# ESP32_LHCbit.net
KiCad netlist of a schematic drawn in Altium Designer
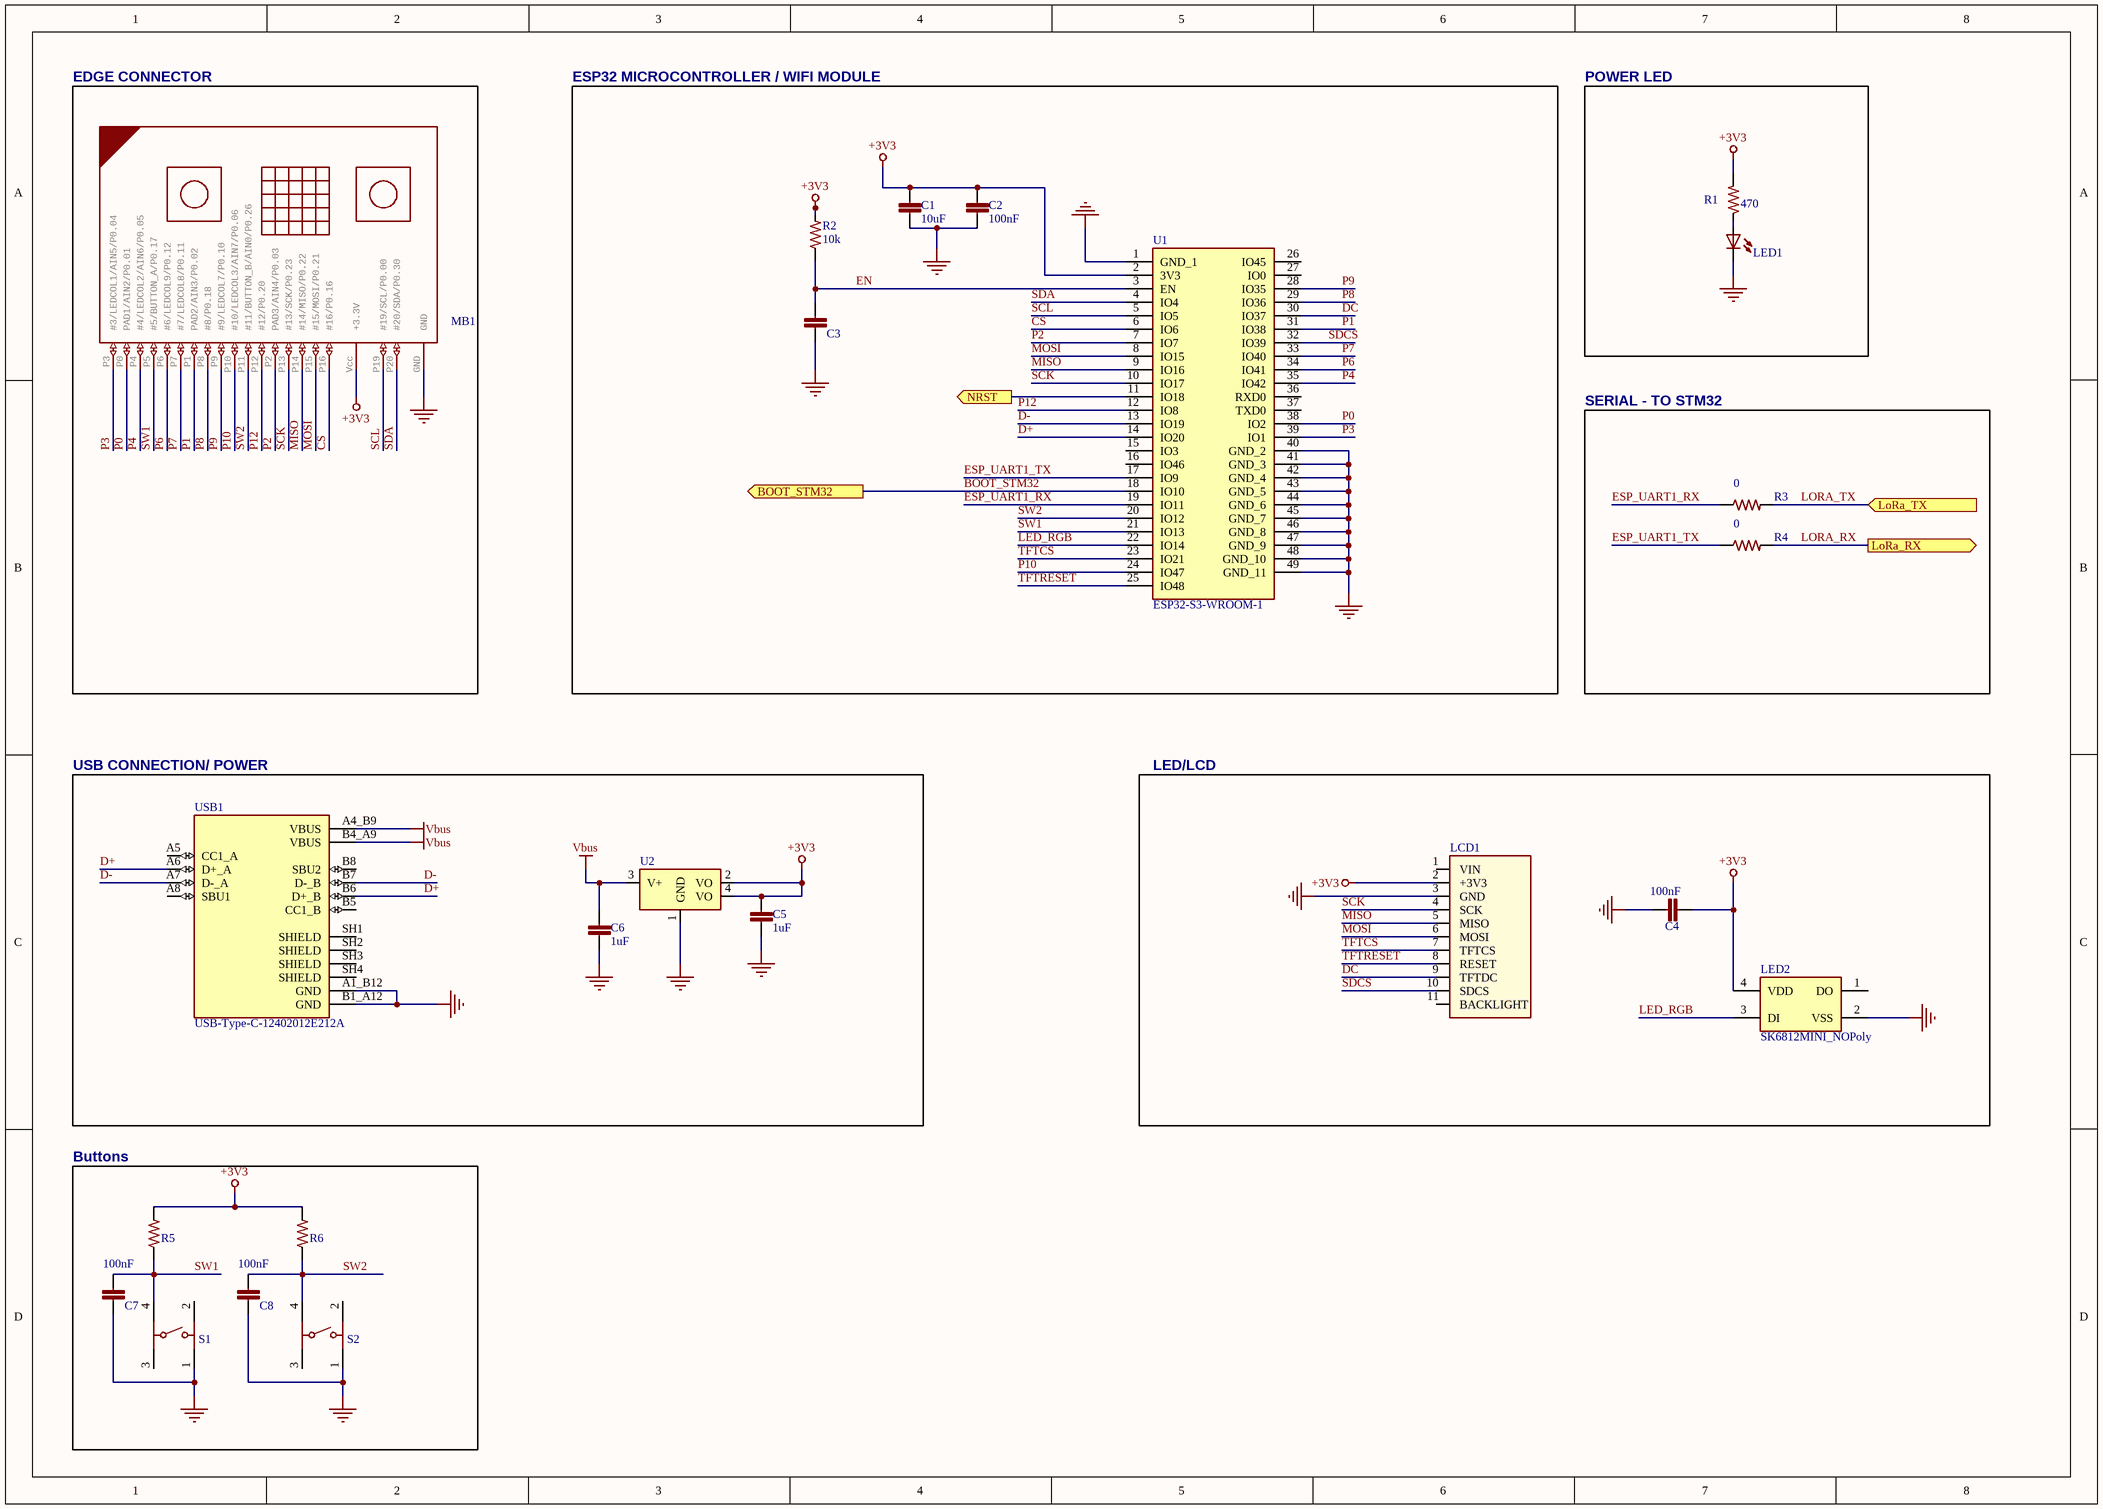
[diagram p0: ESP32_LHCbit.SchDoc]

(export (version "E")
  (design (tool "Eeschema 10.0.6"))
  (components
    (comp (ref "C1")
      (value "10uF")
      (footprint "C0603")
      (fields (field (name "PART NUMBER") "CL10A106KP8NNNC") (field (name "Comment") "C-EUC0603"))
      (libsource (lib "rcl") (part "C-EUC0603"))
    )
    (comp (ref "C2")
      (value "100nF")
      (footprint "C0603")
      (fields (field (name "PART NUMBER") "CC0603KRX7R9BB104") (field (name "Comment") "C-EUC0603"))
      (libsource (lib "rcl") (part "C-EUC0603"))
    )
    (comp (ref "C3")
      (value "C-EUC0402")
      (footprint "C0402")
      (fields (field (name "PART NUMBER") "C0402C104K8"))
      (libsource (lib "rcl") (part "C-EUC0402"))
    )
    (comp (ref "C4")
      (value "100nF")
      (footprint "C0402")
      (fields (field (name "PART NUMBER") "C0402C104K8") (field (name "Comment") "C-EUC0402"))
      (libsource (lib "") (part "C-EUC0402_1"))
    )
    (comp (ref "C5")
      (value "1uF")
      (footprint "C0603")
      (fields (field (name "PART NUMBER") "CL10A105KO8NNNC") (field (name "Comment") "C-EUC0603"))
      (libsource (lib "") (part "C-EUC0603_1"))
    )
    (comp (ref "C6")
      (value "1uF")
      (footprint "C0603")
      (fields (field (name "PART NUMBER") "CL10A105KO8NNNC") (field (name "Comment") "C-EUC0603"))
      (libsource (lib "") (part "C-EUC0603_1"))
    )
    (comp (ref "C7")
      (value "100nF")
      (footprint "C0402")
      (fields (field (name "PART NUMBER") "C0402C104K8") (field (name "Comment") "C-EUC0402"))
      (libsource (lib "rcl") (part "C-EUC0402"))
    )
    (comp (ref "C8")
      (value "100nF")
      (footprint "C0402")
      (fields (field (name "PART NUMBER") "C0402C104K8") (field (name "Comment") "C-EUC0402"))
      (libsource (lib "rcl") (part "C-EUC0402"))
    )
    (comp (ref "LCD1")
      (value "Adafruit 0.96\"  TFT LCD")
      (footprint "ADafruit 0.96 Display")
      (libsource (lib "TE") (part "Adafruit 0.96{dblquote}  TFT LCD"))
    )
    (comp (ref "LED1")
      (value "~")
      (footprint "CHIPLED_0805")
      (fields (field (name "PART NUMBER") "AP2012EC"))
      (libsource (lib "led") (part "LEDCHIPLED_0805"))
    )
    (comp (ref "LED2")
      (value "SK6812MINI_NOPoly")
      (footprint "WS2812BMINI_no_poly")
      (description "SMD RGB (WS2812/SK6812MINI) 3535")
      (fields (field (name "PART NUMBER") "SK6812MINI"))
      (libsource (lib "led") (part "SK6812MINI_NOPoly"))
    )
    (comp (ref "MB1")
      (value "MICRO:BIT_EDGE")
      (footprint "MICROBIT_EDGE")
      (libsource (lib "TE") (part "MICRO{colon}BIT_EDGE"))
    )
    (comp (ref "R1")
      (value "470")
      (footprint "R0603")
      (fields (field (name "PART NUMBER") "RC0603FR-07470RL") (field (name "Comment") "R-US_R0603"))
      (libsource (lib "rcl") (part "R-US_R0603"))
    )
    (comp (ref "R2")
      (value "10k")
      (footprint "R0402")
      (fields (field (name "PART NUMBER") "RC0402FR-0710KL") (field (name "Comment") "R-US_R0402"))
      (libsource (lib "rcl") (part "R-US_R0402"))
    )
    (comp (ref "R3")
      (value "0")
      (footprint "R0402")
      (fields (field (name "PART NUMBER") "PA0402-R-070RL") (field (name "Comment") "R-US_R0402"))
      (libsource (lib "rcl") (part "R-US_R0402"))
    )
    (comp (ref "R4")
      (value "0")
      (footprint "R0402")
      (fields (field (name "PART NUMBER") "PA0402-R-070RL") (field (name "Comment") "R-US_R0402"))
      (libsource (lib "rcl") (part "R-US_R0402"))
    )
    (comp (ref "R5")
      (value "R-US_R0402")
      (footprint "R0402")
      (fields (field (name "PART NUMBER") "RC0402FR-0710KL"))
      (libsource (lib "rcl") (part "R-US_R0402"))
    )
    (comp (ref "R6")
      (value "R-US_R0402")
      (footprint "R0402")
      (fields (field (name "PART NUMBER") "RC0402FR-0710KL"))
      (libsource (lib "rcl") (part "R-US_R0402"))
    )
    (comp (ref "S1")
      (value "DTSM-6")
      (footprint "4301x20438x6_6x6x4.3_DTSM-6")
      (description "WS-TASV 6x6mm Tact Switch, SMD version")
      (libsource (lib "Switches") (part "DTSM-6"))
    )
    (comp (ref "S2")
      (value "DTSM-6")
      (footprint "4301x20438x6_6x6x4.3_DTSM-6")
      (description "WS-TASV 6x6mm Tact Switch, SMD version")
      (libsource (lib "Switches") (part "DTSM-6"))
    )
    (comp (ref "U1")
      (value "ESP32-S3-WROOM-1")
      (footprint "ESP32S3WROOM1N16R2")
      (description "Integrated Circuit")
      (fields (field (name "PART NUMBER") "ESP32-S3-WROOM-1-N16R2"))
      (libsource (lib "TE") (part "ESP32-S3-WROOM-1"))
    )
    (comp (ref "U2")
      (value "NCP1117LP")
      (footprint "SOT223")
      (fields (field (name "PART NUMBER") "TLV1117LV33DCYR"))
      (libsource (lib "TE") (part "NCP1117LP"))
    )
    (comp (ref "USB1")
      (value "USB-Type-C-12402012E212A")
      (footprint "AMPHENOL_12402012E212A")
      (description "USB2.0, Type C")
      (fields (field (name "PART NUMBER") "TYPEC-304-ACP16"))
      (libsource (lib "TE") (part "USB-Type-C-12402012E212A"))
    )
  )
  (nets
    (net (code "1") (name "+3V3") (class "Default")
      (node (ref "C1") (pin "1") (pinfunction "1_1") (pintype "passive"))
      (node (ref "C2") (pin "1") (pinfunction "1_1") (pintype "passive"))
      (node (ref "C4") (pin "2") (pinfunction "2_2") (pintype "passive"))
      (node (ref "C5") (pin "1") (pinfunction "1_1") (pintype "passive"))
      (node (ref "LCD1") (pin "2") (pinfunction "+3V3_2") (pintype "power_in"))
      (node (ref "LED2") (pin "4") (pinfunction "VDD_4") (pintype "passive"))
      (node (ref "MB1") (pin "Vcc") (pinfunction "+3.3V_Vcc") (pintype "power_in"))
      (node (ref "R1") (pin "2") (pinfunction "2_2") (pintype "passive"))
      (node (ref "R2") (pin "2") (pinfunction "2_2") (pintype "passive"))
      (node (ref "R5") (pin "2") (pinfunction "2_2") (pintype "passive"))
      (node (ref "R6") (pin "2") (pinfunction "2_2") (pintype "passive"))
      (node (ref "U1") (pin "2") (pinfunction "3V3_2") (pintype "passive"))
      (node (ref "U2") (pin "2") (pinfunction "VO_2") (pintype "passive"))
      (node (ref "U2") (pin "4") (pinfunction "VO_4") (pintype "passive"))
    )
    (net (code "2") (name "/BOOT_STM32") (class "Default")
      (node (ref "U1") (pin "18") (pinfunction "IO10_18") (pintype "passive"))
    )
    (net (code "3") (name "/CS") (class "Default")
      (node (ref "MB1") (pin "P16") (pinfunction "#16/P0.16_P16") (pintype "bidirectional"))
      (node (ref "U1") (pin "6") (pinfunction "IO6_6") (pintype "passive"))
    )
    (net (code "4") (name "/D+") (class "Default")
      (node (ref "U1") (pin "14") (pinfunction "IO20_14") (pintype "passive"))
      (node (ref "USB1") (pin "A6") (pinfunction "D+_A_A6") (pintype "bidirectional"))
      (node (ref "USB1") (pin "B6") (pinfunction "D+_B_B6") (pintype "bidirectional"))
    )
    (net (code "5") (name "/D-") (class "Default")
      (node (ref "U1") (pin "13") (pinfunction "IO19_13") (pintype "passive"))
      (node (ref "USB1") (pin "A7") (pinfunction "D-_A_A7") (pintype "bidirectional"))
      (node (ref "USB1") (pin "B7") (pinfunction "D-_B_B7") (pintype "bidirectional"))
    )
    (net (code "6") (name "/DC") (class "Default")
      (node (ref "LCD1") (pin "9") (pinfunction "TFTDC_9") (pintype "passive"))
      (node (ref "U1") (pin "30") (pinfunction "IO37_30") (pintype "passive"))
    )
    (net (code "7") (name "/EN") (class "Default")
      (node (ref "C3") (pin "1") (pinfunction "1_1") (pintype "passive"))
      (node (ref "R2") (pin "1") (pinfunction "1_1") (pintype "passive"))
      (node (ref "U1") (pin "3") (pinfunction "EN_3") (pintype "passive"))
    )
    (net (code "8") (name "/ESP_UART1_RX") (class "Default")
      (node (ref "R3") (pin "1") (pinfunction "1_1") (pintype "passive"))
      (node (ref "U1") (pin "19") (pinfunction "IO11_19") (pintype "passive"))
    )
    (net (code "9") (name "/ESP_UART1_TX") (class "Default")
      (node (ref "R4") (pin "1") (pinfunction "1_1") (pintype "passive"))
      (node (ref "U1") (pin "17") (pinfunction "IO9_17") (pintype "passive"))
    )
    (net (code "10") (name "/LED_RGB") (class "Default")
      (node (ref "LED2") (pin "3") (pinfunction "DI_3") (pintype "passive"))
      (node (ref "U1") (pin "22") (pinfunction "IO14_22") (pintype "passive"))
    )
    (net (code "11") (name "/LORA_RX") (class "Default")
      (node (ref "R4") (pin "2") (pinfunction "2_2") (pintype "passive"))
    )
    (net (code "12") (name "/LORA_TX") (class "Default")
      (node (ref "R3") (pin "2") (pinfunction "2_2") (pintype "passive"))
    )
    (net (code "13") (name "/MISO") (class "Default")
      (node (ref "LCD1") (pin "5") (pinfunction "MISO_5") (pintype "passive"))
      (node (ref "MB1") (pin "P14") (pinfunction "#14/MISO/P0.22_P14") (pintype "bidirectional"))
      (node (ref "U1") (pin "9") (pinfunction "IO16_9") (pintype "passive"))
    )
    (net (code "14") (name "/MOSI") (class "Default")
      (node (ref "LCD1") (pin "6") (pinfunction "MOSI_6") (pintype "passive"))
      (node (ref "MB1") (pin "P15") (pinfunction "#15/MOSI/P0.21_P15") (pintype "bidirectional"))
      (node (ref "U1") (pin "8") (pinfunction "IO15_8") (pintype "passive"))
    )
    (net (code "15") (name "/NRST") (class "Default")
      (node (ref "U1") (pin "11") (pinfunction "IO18_11") (pintype "passive"))
    )
    (net (code "16") (name "/P0") (class "Default")
      (node (ref "MB1") (pin "P0") (pinfunction "PAD1/AIN2/P0.01_P0") (pintype "bidirectional"))
      (node (ref "U1") (pin "38") (pinfunction "IO2_38") (pintype "passive"))
    )
    (net (code "17") (name "/P1") (class "Default")
      (node (ref "MB1") (pin "P1") (pinfunction "PAD2/AIN3/P0.02_P1") (pintype "bidirectional"))
      (node (ref "U1") (pin "31") (pinfunction "IO38_31") (pintype "passive"))
    )
    (net (code "18") (name "/P2") (class "Default")
      (node (ref "MB1") (pin "P2") (pinfunction "PAD3/AIN4/P0.03_P2") (pintype "bidirectional"))
      (node (ref "U1") (pin "7") (pinfunction "IO7_7") (pintype "passive"))
    )
    (net (code "19") (name "/P3") (class "Default")
      (node (ref "MB1") (pin "P3") (pinfunction "#3/LEDCOL1/AIN5/P0.04_P3") (pintype "bidirectional"))
      (node (ref "U1") (pin "39") (pinfunction "IO1_39") (pintype "passive"))
    )
    (net (code "20") (name "/P4") (class "Default")
      (node (ref "MB1") (pin "P4") (pinfunction "#4/LEDCOL2/AIN6/P0.05_P4") (pintype "bidirectional"))
      (node (ref "U1") (pin "35") (pinfunction "IO42_35") (pintype "passive"))
    )
    (net (code "21") (name "/P6") (class "Default")
      (node (ref "MB1") (pin "P6") (pinfunction "#6/LEDCOL9/P0.12_P6") (pintype "bidirectional"))
      (node (ref "U1") (pin "34") (pinfunction "IO41_34") (pintype "passive"))
    )
    (net (code "22") (name "/P7") (class "Default")
      (node (ref "MB1") (pin "P7") (pinfunction "#7/LEDCOL8/P0.11_P7") (pintype "bidirectional"))
      (node (ref "U1") (pin "33") (pinfunction "IO40_33") (pintype "passive"))
    )
    (net (code "23") (name "/P8") (class "Default")
      (node (ref "MB1") (pin "P8") (pinfunction "#8/P0.18_P8") (pintype "bidirectional"))
      (node (ref "U1") (pin "29") (pinfunction "IO36_29") (pintype "passive"))
    )
    (net (code "24") (name "/P9") (class "Default")
      (node (ref "MB1") (pin "P9") (pinfunction "#9/LEDCOL7/P0.10_P9") (pintype "bidirectional"))
      (node (ref "U1") (pin "28") (pinfunction "IO35_28") (pintype "passive"))
    )
    (net (code "25") (name "/P10") (class "Default")
      (node (ref "MB1") (pin "P10") (pinfunction "#10/LEDCOL3/AIN7/P0.06_P10") (pintype "bidirectional"))
      (node (ref "U1") (pin "24") (pinfunction "IO47_24") (pintype "passive"))
    )
    (net (code "26") (name "/P12") (class "Default")
      (node (ref "MB1") (pin "P12") (pinfunction "#12/P0.20_P12") (pintype "bidirectional"))
      (node (ref "U1") (pin "12") (pinfunction "IO8_12") (pintype "passive"))
    )
    (net (code "27") (name "/SCK") (class "Default")
      (node (ref "LCD1") (pin "4") (pinfunction "SCK_4") (pintype "passive"))
      (node (ref "MB1") (pin "P13") (pinfunction "#13/SCK/P0.23_P13") (pintype "bidirectional"))
      (node (ref "U1") (pin "10") (pinfunction "IO17_10") (pintype "passive"))
    )
    (net (code "28") (name "/SCL") (class "Default")
      (node (ref "MB1") (pin "P19") (pinfunction "#19/SCL/P0.00_P19") (pintype "bidirectional"))
      (node (ref "U1") (pin "5") (pinfunction "IO5_5") (pintype "passive"))
    )
    (net (code "29") (name "/SDA") (class "Default")
      (node (ref "MB1") (pin "P20") (pinfunction "#20/SDA/P0.30_P20") (pintype "bidirectional"))
      (node (ref "U1") (pin "4") (pinfunction "IO4_4") (pintype "passive"))
    )
    (net (code "30") (name "/SDCS") (class "Default")
      (node (ref "LCD1") (pin "10") (pinfunction "SDCS_10") (pintype "passive"))
      (node (ref "U1") (pin "32") (pinfunction "IO39_32") (pintype "passive"))
    )
    (net (code "31") (name "/SW1") (class "Default")
      (node (ref "C7") (pin "1") (pinfunction "1_1") (pintype "passive"))
      (node (ref "MB1") (pin "P5") (pinfunction "#5/BUTTON_A/P0.17_P5") (pintype "bidirectional"))
      (node (ref "R5") (pin "1") (pinfunction "1_1") (pintype "passive"))
      (node (ref "S1") (pin "4") (pinfunction "4_4") (pintype "passive"))
      (node (ref "U1") (pin "21") (pinfunction "IO13_21") (pintype "passive"))
    )
    (net (code "32") (name "/SW2") (class "Default")
      (node (ref "C8") (pin "1") (pinfunction "1_1") (pintype "passive"))
      (node (ref "MB1") (pin "P11") (pinfunction "#11/BUTTON_B/AIN0/P0.26_P11") (pintype "bidirectional"))
      (node (ref "R6") (pin "1") (pinfunction "1_1") (pintype "passive"))
      (node (ref "S2") (pin "4") (pinfunction "4_4") (pintype "passive"))
      (node (ref "U1") (pin "20") (pinfunction "IO12_20") (pintype "passive"))
    )
    (net (code "33") (name "/TFTCS") (class "Default")
      (node (ref "LCD1") (pin "7") (pinfunction "TFTCS_7") (pintype "passive"))
      (node (ref "U1") (pin "23") (pinfunction "IO21_23") (pintype "passive"))
    )
    (net (code "34") (name "/TFTRESET") (class "Default")
      (node (ref "LCD1") (pin "8") (pinfunction "RESET_8") (pintype "passive"))
      (node (ref "U1") (pin "25") (pinfunction "IO48_25") (pintype "passive"))
    )
    (net (code "35") (name "GND") (class "Default")
      (node (ref "C1") (pin "2") (pinfunction "2_2") (pintype "passive"))
      (node (ref "C2") (pin "2") (pinfunction "2_2") (pintype "passive"))
      (node (ref "C3") (pin "2") (pinfunction "2_2") (pintype "passive"))
      (node (ref "C4") (pin "1") (pinfunction "1_1") (pintype "passive"))
      (node (ref "C5") (pin "2") (pinfunction "2_2") (pintype "passive"))
      (node (ref "C6") (pin "2") (pinfunction "2_2") (pintype "passive"))
      (node (ref "C7") (pin "2") (pinfunction "2_2") (pintype "passive"))
      (node (ref "C8") (pin "2") (pinfunction "2_2") (pintype "passive"))
      (node (ref "LCD1") (pin "3") (pinfunction "GND_3") (pintype "passive"))
      (node (ref "LED1") (pin "C") (pinfunction "C_C") (pintype "passive"))
      (node (ref "LED2") (pin "2") (pinfunction "VSS_2") (pintype "passive"))
      (node (ref "MB1") (pin "GND") (pinfunction "GND_GND") (pintype "power_in"))
      (node (ref "S1") (pin "1") (pinfunction "1_1") (pintype "passive"))
      (node (ref "S2") (pin "1") (pinfunction "1_1") (pintype "passive"))
      (node (ref "U1") (pin "1") (pinfunction "GND_1_1") (pintype "passive"))
      (node (ref "U1") (pin "40") (pinfunction "GND_2_40") (pintype "passive"))
      (node (ref "U1") (pin "41") (pinfunction "GND_3_41") (pintype "passive"))
      (node (ref "U1") (pin "42") (pinfunction "GND_4_42") (pintype "passive"))
      (node (ref "U1") (pin "43") (pinfunction "GND_5_43") (pintype "passive"))
      (node (ref "U1") (pin "44") (pinfunction "GND_6_44") (pintype "passive"))
      (node (ref "U1") (pin "45") (pinfunction "GND_7_45") (pintype "passive"))
      (node (ref "U1") (pin "46") (pinfunction "GND_8_46") (pintype "passive"))
      (node (ref "U1") (pin "47") (pinfunction "GND_9_47") (pintype "passive"))
      (node (ref "U1") (pin "48") (pinfunction "GND_10_48") (pintype "passive"))
      (node (ref "U1") (pin "49") (pinfunction "GND_11_49") (pintype "passive"))
      (node (ref "U2") (pin "1") (pinfunction "GND_1") (pintype "power_in"))
      (node (ref "USB1") (pin "A1_B12") (pinfunction "GND_A1_B12") (pintype "power_in"))
      (node (ref "USB1") (pin "B1_A12") (pinfunction "GND_B1_A12") (pintype "power_in"))
    )
    (net (code "36") (name "Net-(LED1-PadA)") (class "Default")
      (node (ref "LED1") (pin "A") (pinfunction "A_A") (pintype "passive"))
      (node (ref "R1") (pin "1") (pinfunction "1_1") (pintype "passive"))
    )
    (net (code "37") (name "Vbus") (class "Default")
      (node (ref "C6") (pin "1") (pinfunction "1_1") (pintype "passive"))
      (node (ref "U2") (pin "3") (pinfunction "V+_3") (pintype "power_in"))
      (node (ref "USB1") (pin "A4_B9") (pinfunction "VBUS_A4_B9") (pintype "power_in"))
      (node (ref "USB1") (pin "B4_A9") (pinfunction "VBUS_B4_A9") (pintype "power_in"))
    )
    (net (code "38") (name "unconnected-(LCD1-BACKLIGHT-Pad11)") (class "Default")
      (node (ref "LCD1") (pin "11") (pinfunction "BACKLIGHT_11") (pintype "passive"))
    )
    (net (code "39") (name "unconnected-(LCD1-VIN-Pad1)") (class "Default")
      (node (ref "LCD1") (pin "1") (pinfunction "VIN_1") (pintype "power_in"))
    )
    (net (code "40") (name "unconnected-(LED2-DO-Pad1)") (class "Default")
      (node (ref "LED2") (pin "1") (pinfunction "DO_1") (pintype "passive"))
    )
    (net (code "41") (name "unconnected-(S1-Pad2)") (class "Default")
      (node (ref "S1") (pin "2") (pinfunction "2_2") (pintype "passive"))
    )
    (net (code "42") (name "unconnected-(S1-Pad3)") (class "Default")
      (node (ref "S1") (pin "3") (pinfunction "3_3") (pintype "passive"))
    )
    (net (code "43") (name "unconnected-(S2-Pad2)") (class "Default")
      (node (ref "S2") (pin "2") (pinfunction "2_2") (pintype "passive"))
    )
    (net (code "44") (name "unconnected-(S2-Pad3)") (class "Default")
      (node (ref "S2") (pin "3") (pinfunction "3_3") (pintype "passive"))
    )
    (net (code "45") (name "unconnected-(U1-IO0-Pad27)") (class "Default")
      (node (ref "U1") (pin "27") (pinfunction "IO0_27") (pintype "passive"))
    )
    (net (code "46") (name "unconnected-(U1-IO3-Pad15)") (class "Default")
      (node (ref "U1") (pin "15") (pinfunction "IO3_15") (pintype "passive"))
    )
    (net (code "47") (name "unconnected-(U1-IO45-Pad26)") (class "Default")
      (node (ref "U1") (pin "26") (pinfunction "IO45_26") (pintype "passive"))
    )
    (net (code "48") (name "unconnected-(U1-IO46-Pad16)") (class "Default")
      (node (ref "U1") (pin "16") (pinfunction "IO46_16") (pintype "passive"))
    )
    (net (code "49") (name "unconnected-(U1-RXD0-Pad36)") (class "Default")
      (node (ref "U1") (pin "36") (pinfunction "RXD0_36") (pintype "passive"))
    )
    (net (code "50") (name "unconnected-(U1-TXD0-Pad37)") (class "Default")
      (node (ref "U1") (pin "37") (pinfunction "TXD0_37") (pintype "passive"))
    )
    (net (code "51") (name "unconnected-(USB1-CC1_A-PadA5)") (class "Default")
      (node (ref "USB1") (pin "A5") (pinfunction "CC1_A_A5") (pintype "bidirectional"))
    )
    (net (code "52") (name "unconnected-(USB1-CC1_B-PadB5)") (class "Default")
      (node (ref "USB1") (pin "B5") (pinfunction "CC1_B_B5") (pintype "bidirectional"))
    )
    (net (code "53") (name "unconnected-(USB1-SBU1-PadA8)") (class "Default")
      (node (ref "USB1") (pin "A8") (pinfunction "SBU1_A8") (pintype "bidirectional"))
    )
    (net (code "54") (name "unconnected-(USB1-SBU2-PadB8)") (class "Default")
      (node (ref "USB1") (pin "B8") (pinfunction "SBU2_B8") (pintype "bidirectional"))
    )
    (net (code "55") (name "unconnected-(USB1-SHIELD-PadSH1)") (class "Default")
      (node (ref "USB1") (pin "SH1") (pinfunction "SHIELD_SH1") (pintype "passive"))
    )
    (net (code "56") (name "unconnected-(USB1-SHIELD-PadSH2)") (class "Default")
      (node (ref "USB1") (pin "SH2") (pinfunction "SHIELD_SH2") (pintype "passive"))
    )
    (net (code "57") (name "unconnected-(USB1-SHIELD-PadSH3)") (class "Default")
      (node (ref "USB1") (pin "SH3") (pinfunction "SHIELD_SH3") (pintype "passive"))
    )
    (net (code "58") (name "unconnected-(USB1-SHIELD-PadSH4)") (class "Default")
      (node (ref "USB1") (pin "SH4") (pinfunction "SHIELD_SH4") (pintype "passive"))
    )
  )
)
